# Grove_-_Q_Touch_Sensor_v1_0.net
KiCad netlist of a schematic drawn in EAGLE
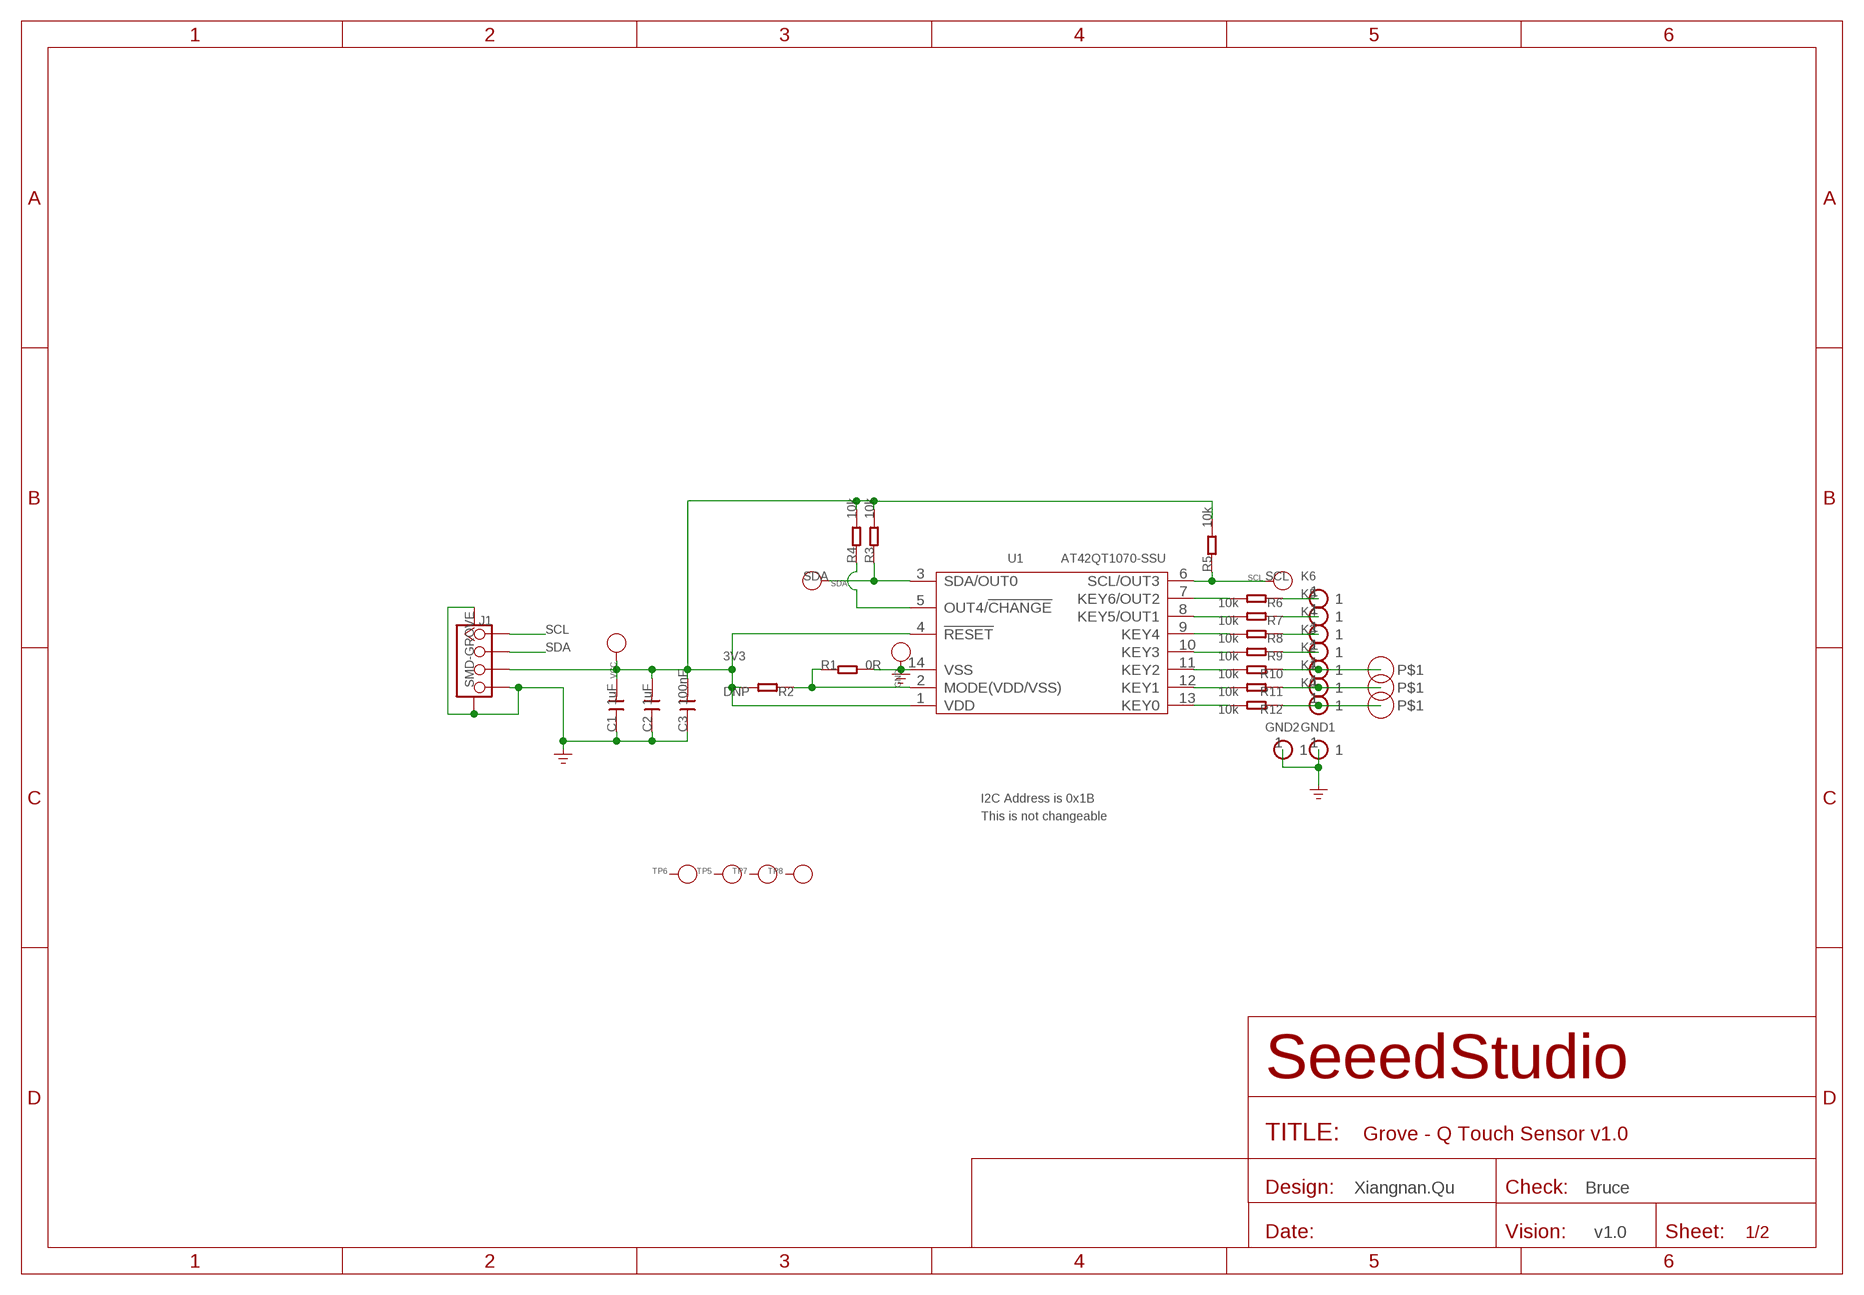
[diagram p0: schematic, sheet 1]
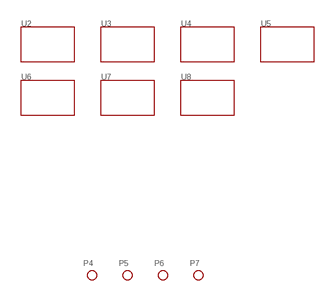
[diagram p1: schematic, sheet 2]

(export (version "E")
  (design (tool "Eeschema 10.0.6"))
  (components
    (comp (ref "C1")
      (value "1uF")
      (footprint "eagle-import:C0603")
      (libsource (lib "eagle-import") (part "C-0603"))
    )
    (comp (ref "C2")
      (value "1uF")
      (footprint "eagle-import:C0603")
      (libsource (lib "eagle-import") (part "C-0603"))
    )
    (comp (ref "C3")
      (value "100nF")
      (footprint "eagle-import:C0603")
      (libsource (lib "eagle-import") (part "C-0603"))
    )
    (comp (ref "GND")
      (value "PAD-TEST-POINT'4545'")
      (footprint "eagle-import:TP_4545")
      (fields (field (name "PARTNO") "DNP"))
      (libsource (lib "eagle-import") (part "PAD-TEST-POINT'4545'"))
    )
    (comp (ref "GND1")
      (value "HEADER-1P-35")
      (footprint "eagle-import:1P-65_35MIL")
      (libsource (lib "eagle-import") (part "HEADER-1P-35"))
    )
    (comp (ref "GND2")
      (value "HEADER-1P-35")
      (footprint "eagle-import:1P-65_35MIL")
      (libsource (lib "eagle-import") (part "HEADER-1P-35"))
    )
    (comp (ref "J1")
      (value "SMD-GROVE")
      (footprint "eagle-import:4P-SMD-2.0")
      (libsource (lib "eagle-import") (part "TWIG-4P-2.0-SMD-FEMALE-REINFORCE'DD'"))
    )
    (comp (ref "K0")
      (value "HEADER-1P-35")
      (footprint "eagle-import:1P-65_35MIL")
      (libsource (lib "eagle-import") (part "HEADER-1P-35"))
    )
    (comp (ref "K1")
      (value "HEADER-1P-35")
      (footprint "eagle-import:1P-65_35MIL")
      (libsource (lib "eagle-import") (part "HEADER-1P-35"))
    )
    (comp (ref "K2")
      (value "HEADER-1P-35")
      (footprint "eagle-import:1P-65_35MIL")
      (libsource (lib "eagle-import") (part "HEADER-1P-35"))
    )
    (comp (ref "K3")
      (value "HEADER-1P-35")
      (footprint "eagle-import:1P-65_35MIL")
      (libsource (lib "eagle-import") (part "HEADER-1P-35"))
    )
    (comp (ref "K4")
      (value "HEADER-1P-35")
      (footprint "eagle-import:1P-65_35MIL")
      (libsource (lib "eagle-import") (part "HEADER-1P-35"))
    )
    (comp (ref "K5")
      (value "HEADER-1P-35")
      (footprint "eagle-import:1P-65_35MIL")
      (libsource (lib "eagle-import") (part "HEADER-1P-35"))
    )
    (comp (ref "K6")
      (value "HEADER-1P-35")
      (footprint "eagle-import:1P-65_35MIL")
      (libsource (lib "eagle-import") (part "HEADER-1P-35"))
    )
    (comp (ref "P1")
      (value "PAD-HOLE")
      (footprint "eagle-import:1P-D6MM")
      (libsource (lib "eagle-import") (part "PAD-HOLE"))
    )
    (comp (ref "P2")
      (value "PAD-HOLE")
      (footprint "eagle-import:1P-D6MM")
      (libsource (lib "eagle-import") (part "PAD-HOLE"))
    )
    (comp (ref "P3")
      (value "PAD-HOLE")
      (footprint "eagle-import:1P-D6MM")
      (libsource (lib "eagle-import") (part "PAD-HOLE"))
    )
    (comp (ref "R1")
      (value "0R")
      (footprint "eagle-import:R0603")
      (libsource (lib "eagle-import") (part "R-0603"))
    )
    (comp (ref "R2")
      (value "DNP")
      (footprint "eagle-import:R0603")
      (libsource (lib "eagle-import") (part "R-0603"))
    )
    (comp (ref "R3")
      (value "10k")
      (footprint "eagle-import:R0603")
      (libsource (lib "eagle-import") (part "R-0603"))
    )
    (comp (ref "R4")
      (value "10k")
      (footprint "eagle-import:R0603")
      (libsource (lib "eagle-import") (part "R-0603"))
    )
    (comp (ref "R5")
      (value "10k")
      (footprint "eagle-import:R0603")
      (libsource (lib "eagle-import") (part "R-0603"))
    )
    (comp (ref "R6")
      (value "10k")
      (footprint "eagle-import:R0603")
      (libsource (lib "eagle-import") (part "R-0603"))
    )
    (comp (ref "R7")
      (value "10k")
      (footprint "eagle-import:R0603")
      (libsource (lib "eagle-import") (part "R-0603"))
    )
    (comp (ref "R8")
      (value "10k")
      (footprint "eagle-import:R0603")
      (libsource (lib "eagle-import") (part "R-0603"))
    )
    (comp (ref "R9")
      (value "10k")
      (footprint "eagle-import:R0603")
      (libsource (lib "eagle-import") (part "R-0603"))
    )
    (comp (ref "R10")
      (value "10k")
      (footprint "eagle-import:R0603")
      (libsource (lib "eagle-import") (part "R-0603"))
    )
    (comp (ref "R11")
      (value "10k")
      (footprint "eagle-import:R0603")
      (libsource (lib "eagle-import") (part "R-0603"))
    )
    (comp (ref "R12")
      (value "10k")
      (footprint "eagle-import:R0603")
      (libsource (lib "eagle-import") (part "R-0603"))
    )
    (comp (ref "SCL")
      (value "PAD-TEST-POINT'4545'")
      (footprint "eagle-import:TP_4545")
      (fields (field (name "PARTNO") "DNP"))
      (libsource (lib "eagle-import") (part "PAD-TEST-POINT'4545'"))
    )
    (comp (ref "SDA")
      (value "PAD-TEST-POINT'4545'")
      (footprint "eagle-import:TP_4545")
      (fields (field (name "PARTNO") "DNP"))
      (libsource (lib "eagle-import") (part "PAD-TEST-POINT'4545'"))
    )
    (comp (ref "TP5")
      (value "PAD-TEST-POINT'4545'")
      (footprint "eagle-import:TP_4545")
      (fields (field (name "PARTNO") "DNP"))
      (libsource (lib "eagle-import") (part "PAD-TEST-POINT'4545'"))
    )
    (comp (ref "TP6")
      (value "PAD-TEST-POINT'4545'")
      (footprint "eagle-import:TP_4545")
      (fields (field (name "PARTNO") "DNP"))
      (libsource (lib "eagle-import") (part "PAD-TEST-POINT'4545'"))
    )
    (comp (ref "TP7")
      (value "PAD-TEST-POINT'4545'")
      (footprint "eagle-import:TP_4545")
      (fields (field (name "PARTNO") "DNP"))
      (libsource (lib "eagle-import") (part "PAD-TEST-POINT'4545'"))
    )
    (comp (ref "TP8")
      (value "PAD-TEST-POINT'4545'")
      (footprint "eagle-import:TP_4545")
      (fields (field (name "PARTNO") "DNP"))
      (libsource (lib "eagle-import") (part "PAD-TEST-POINT'4545'"))
    )
    (comp (ref "U1")
      (value "AT42QT1070-SSU")
      (footprint "eagle-import:SOIC14")
      (libsource (lib "eagle-import") (part "AT42QT1070SSU"))
    )
    (comp (ref "VCC")
      (value "PAD-TEST-POINT'4545'")
      (footprint "eagle-import:TP_4545")
      (fields (field (name "PARTNO") "DNP"))
      (libsource (lib "eagle-import") (part "PAD-TEST-POINT'4545'"))
    )
    (comp (ref "P4")
      (value "PAD-MARK")
      (footprint "eagle-import:ROUND-MARK-1.0")
      (fields (field (name "PARTNO") "DNP"))
      (libsource (lib "eagle-import") (part "PAD-MARK"))
    )
    (comp (ref "P5")
      (value "PAD-MARK")
      (footprint "eagle-import:ROUND-MARK-1.0")
      (fields (field (name "PARTNO") "DNP"))
      (libsource (lib "eagle-import") (part "PAD-MARK"))
    )
    (comp (ref "P6")
      (value "PAD-MARK")
      (footprint "eagle-import:ROUND-MARK-1.0")
      (fields (field (name "PARTNO") "DNP"))
      (libsource (lib "eagle-import") (part "PAD-MARK"))
    )
    (comp (ref "P7")
      (value "PAD-MARK")
      (footprint "eagle-import:ROUND-MARK-1.0")
      (fields (field (name "PARTNO") "DNP"))
      (libsource (lib "eagle-import") (part "PAD-MARK"))
    )
    (comp (ref "U2")
      (value "TWIG'2U'")
      (footprint "eagle-import:GROVE-TEST-PLATFORM")
      (libsource (lib "eagle-import") (part "TWIG'2U'"))
    )
    (comp (ref "U3")
      (value "TWIG'2U'")
      (footprint "eagle-import:GROVE-TEST-PLATFORM")
      (libsource (lib "eagle-import") (part "TWIG'2U'"))
    )
    (comp (ref "U4")
      (value "TWIG'2U'")
      (footprint "eagle-import:GROVE-TEST-PLATFORM")
      (libsource (lib "eagle-import") (part "TWIG'2U'"))
    )
    (comp (ref "U5")
      (value "TWIG'2U'")
      (footprint "eagle-import:GROVE-TEST-PLATFORM")
      (libsource (lib "eagle-import") (part "TWIG'2U'"))
    )
    (comp (ref "U6")
      (value "TWIG'2U'")
      (footprint "eagle-import:GROVE-TEST-PLATFORM")
      (libsource (lib "eagle-import") (part "TWIG'2U'"))
    )
    (comp (ref "U7")
      (value "TWIG'2U'")
      (footprint "eagle-import:GROVE-TEST-PLATFORM")
      (libsource (lib "eagle-import") (part "TWIG'2U'"))
    )
    (comp (ref "U8")
      (value "TWIG'2U'")
      (footprint "eagle-import:GROVE-TEST-PLATFORM")
      (libsource (lib "eagle-import") (part "TWIG'2U'"))
    )
  )
  (nets
    (net (code "1") (name "3V3") (class "Default")
      (node (ref "C1") (pin "2") (pinfunction "2_2") (pintype "passive"))
      (node (ref "C2") (pin "2") (pinfunction "2_2") (pintype "passive"))
      (node (ref "C3") (pin "2") (pinfunction "2_2") (pintype "passive"))
      (node (ref "J1") (pin "3") (pinfunction "3_3") (pintype "bidirectional"))
      (node (ref "R2") (pin "2") (pinfunction "2_2") (pintype "passive"))
      (node (ref "R3") (pin "2") (pinfunction "2_2") (pintype "passive"))
      (node (ref "R4") (pin "2") (pinfunction "2_2") (pintype "passive"))
      (node (ref "R5") (pin "2") (pinfunction "2_2") (pintype "passive"))
      (node (ref "U1") (pin "1") (pinfunction "VDD_1") (pintype "bidirectional"))
      (node (ref "U1") (pin "4") (pinfunction "~{RESET}_4") (pintype "bidirectional"))
      (node (ref "VCC") (pin "T") (pinfunction "T_T") (pintype "bidirectional"))
    )
    (net (code "2") (name "GND") (class "Default")
      (node (ref "C1") (pin "1") (pinfunction "1_1") (pintype "passive"))
      (node (ref "C2") (pin "1") (pinfunction "1_1") (pintype "passive"))
      (node (ref "C3") (pin "1") (pinfunction "1_1") (pintype "passive"))
      (node (ref "GND") (pin "T") (pinfunction "T_T") (pintype "bidirectional"))
      (node (ref "GND1") (pin "1") (pinfunction "1_1") (pintype "bidirectional"))
      (node (ref "GND2") (pin "1") (pinfunction "1_1") (pintype "bidirectional"))
      (node (ref "J1") (pin "4") (pinfunction "4_4") (pintype "bidirectional"))
      (node (ref "J1") (pin "SS1") (pinfunction "SS1_SS1") (pintype "bidirectional"))
      (node (ref "J1") (pin "SS2") (pinfunction "SS2_SS2") (pintype "bidirectional"))
      (node (ref "R1") (pin "2") (pinfunction "2_2") (pintype "passive"))
      (node (ref "U1") (pin "14") (pinfunction "VSS_14") (pintype "bidirectional"))
    )
    (net (code "3") (name "Net-(K3-Pad1)") (class "Default")
      (node (ref "K3") (pin "1") (pinfunction "1_1") (pintype "bidirectional"))
      (node (ref "R9") (pin "1") (pinfunction "1_1") (pintype "passive"))
    )
    (net (code "4") (name "Net-(K4-Pad1)") (class "Default")
      (node (ref "K4") (pin "1") (pinfunction "1_1") (pintype "bidirectional"))
      (node (ref "R8") (pin "1") (pinfunction "1_1") (pintype "passive"))
    )
    (net (code "5") (name "Net-(K5-Pad1)") (class "Default")
      (node (ref "K5") (pin "1") (pinfunction "1_1") (pintype "bidirectional"))
      (node (ref "R7") (pin "1") (pinfunction "1_1") (pintype "passive"))
    )
    (net (code "6") (name "Net-(K6-Pad1)") (class "Default")
      (node (ref "K6") (pin "1") (pinfunction "1_1") (pintype "bidirectional"))
      (node (ref "R6") (pin "1") (pinfunction "1_1") (pintype "passive"))
    )
    (net (code "7") (name "Net-(P1-P$1)") (class "Default")
      (node (ref "K2") (pin "1") (pinfunction "1_1") (pintype "bidirectional"))
      (node (ref "P1") (pin "1") (pinfunction "P$1_1") (pintype "bidirectional"))
      (node (ref "R10") (pin "1") (pinfunction "1_1") (pintype "passive"))
    )
    (net (code "8") (name "Net-(P2-P$1)") (class "Default")
      (node (ref "K1") (pin "1") (pinfunction "1_1") (pintype "bidirectional"))
      (node (ref "P2") (pin "1") (pinfunction "P$1_1") (pintype "bidirectional"))
      (node (ref "R11") (pin "1") (pinfunction "1_1") (pintype "passive"))
    )
    (net (code "9") (name "Net-(P3-P$1)") (class "Default")
      (node (ref "K0") (pin "1") (pinfunction "1_1") (pintype "bidirectional"))
      (node (ref "P3") (pin "1") (pinfunction "P$1_1") (pintype "bidirectional"))
      (node (ref "R12") (pin "1") (pinfunction "1_1") (pintype "passive"))
    )
    (net (code "10") (name "Net-(U1-KEY0)") (class "Default")
      (node (ref "R12") (pin "2") (pinfunction "2_2") (pintype "passive"))
      (node (ref "U1") (pin "13") (pinfunction "KEY0_13") (pintype "bidirectional"))
    )
    (net (code "11") (name "Net-(U1-KEY1)") (class "Default")
      (node (ref "R11") (pin "2") (pinfunction "2_2") (pintype "passive"))
      (node (ref "U1") (pin "12") (pinfunction "KEY1_12") (pintype "bidirectional"))
    )
    (net (code "12") (name "Net-(U1-KEY2)") (class "Default")
      (node (ref "R10") (pin "2") (pinfunction "2_2") (pintype "passive"))
      (node (ref "U1") (pin "11") (pinfunction "KEY2_11") (pintype "bidirectional"))
    )
    (net (code "13") (name "Net-(U1-KEY3)") (class "Default")
      (node (ref "R9") (pin "2") (pinfunction "2_2") (pintype "passive"))
      (node (ref "U1") (pin "10") (pinfunction "KEY3_10") (pintype "bidirectional"))
    )
    (net (code "14") (name "Net-(U1-KEY4)") (class "Default")
      (node (ref "R8") (pin "2") (pinfunction "2_2") (pintype "passive"))
      (node (ref "U1") (pin "9") (pinfunction "KEY4_9") (pintype "bidirectional"))
    )
    (net (code "15") (name "Net-(U1-KEY5{slash}OUT1)") (class "Default")
      (node (ref "R7") (pin "2") (pinfunction "2_2") (pintype "passive"))
      (node (ref "U1") (pin "8") (pinfunction "KEY5/OUT1_8") (pintype "bidirectional"))
    )
    (net (code "16") (name "Net-(U1-KEY6{slash}OUT2)") (class "Default")
      (node (ref "R6") (pin "2") (pinfunction "2_2") (pintype "passive"))
      (node (ref "U1") (pin "7") (pinfunction "KEY6/OUT2_7") (pintype "bidirectional"))
    )
    (net (code "17") (name "Net-(U1-MODE(VDD{slash}VSS))") (class "Default")
      (node (ref "R1") (pin "1") (pinfunction "1_1") (pintype "passive"))
      (node (ref "R2") (pin "1") (pinfunction "1_1") (pintype "passive"))
      (node (ref "U1") (pin "2") (pinfunction "MODE(VDD/VSS)_2") (pintype "bidirectional"))
    )
    (net (code "18") (name "Net-(U1-OUT4{slash}~{CHANGE})") (class "Default")
      (node (ref "R4") (pin "1") (pinfunction "1_1") (pintype "passive"))
      (node (ref "U1") (pin "5") (pinfunction "OUT4/~{CHANGE}_5") (pintype "bidirectional"))
    )
    (net (code "19") (name "SCL") (class "Default")
      (node (ref "J1") (pin "1") (pinfunction "1_1") (pintype "bidirectional"))
      (node (ref "R5") (pin "1") (pinfunction "1_1") (pintype "passive"))
      (node (ref "SCL") (pin "T") (pinfunction "T_T") (pintype "bidirectional"))
      (node (ref "U1") (pin "6") (pinfunction "SCL/OUT3_6") (pintype "bidirectional"))
    )
    (net (code "20") (name "SDA") (class "Default")
      (node (ref "J1") (pin "2") (pinfunction "2_2") (pintype "bidirectional"))
      (node (ref "R3") (pin "1") (pinfunction "1_1") (pintype "passive"))
      (node (ref "SDA") (pin "T") (pinfunction "T_T") (pintype "bidirectional"))
      (node (ref "U1") (pin "3") (pinfunction "SDA/OUT0_3") (pintype "bidirectional"))
    )
    (net (code "21") (name "unconnected-(TP5-PadT)") (class "Default")
      (node (ref "TP5") (pin "T") (pinfunction "T_T") (pintype "bidirectional"))
    )
    (net (code "22") (name "unconnected-(TP6-PadT)") (class "Default")
      (node (ref "TP6") (pin "T") (pinfunction "T_T") (pintype "bidirectional"))
    )
    (net (code "23") (name "unconnected-(TP7-PadT)") (class "Default")
      (node (ref "TP7") (pin "T") (pinfunction "T_T") (pintype "bidirectional"))
    )
    (net (code "24") (name "unconnected-(TP8-PadT)") (class "Default")
      (node (ref "TP8") (pin "T") (pinfunction "T_T") (pintype "bidirectional"))
    )
  )
)
